# 2.net
KiCad netlist of a schematic drawn in Altium Designer
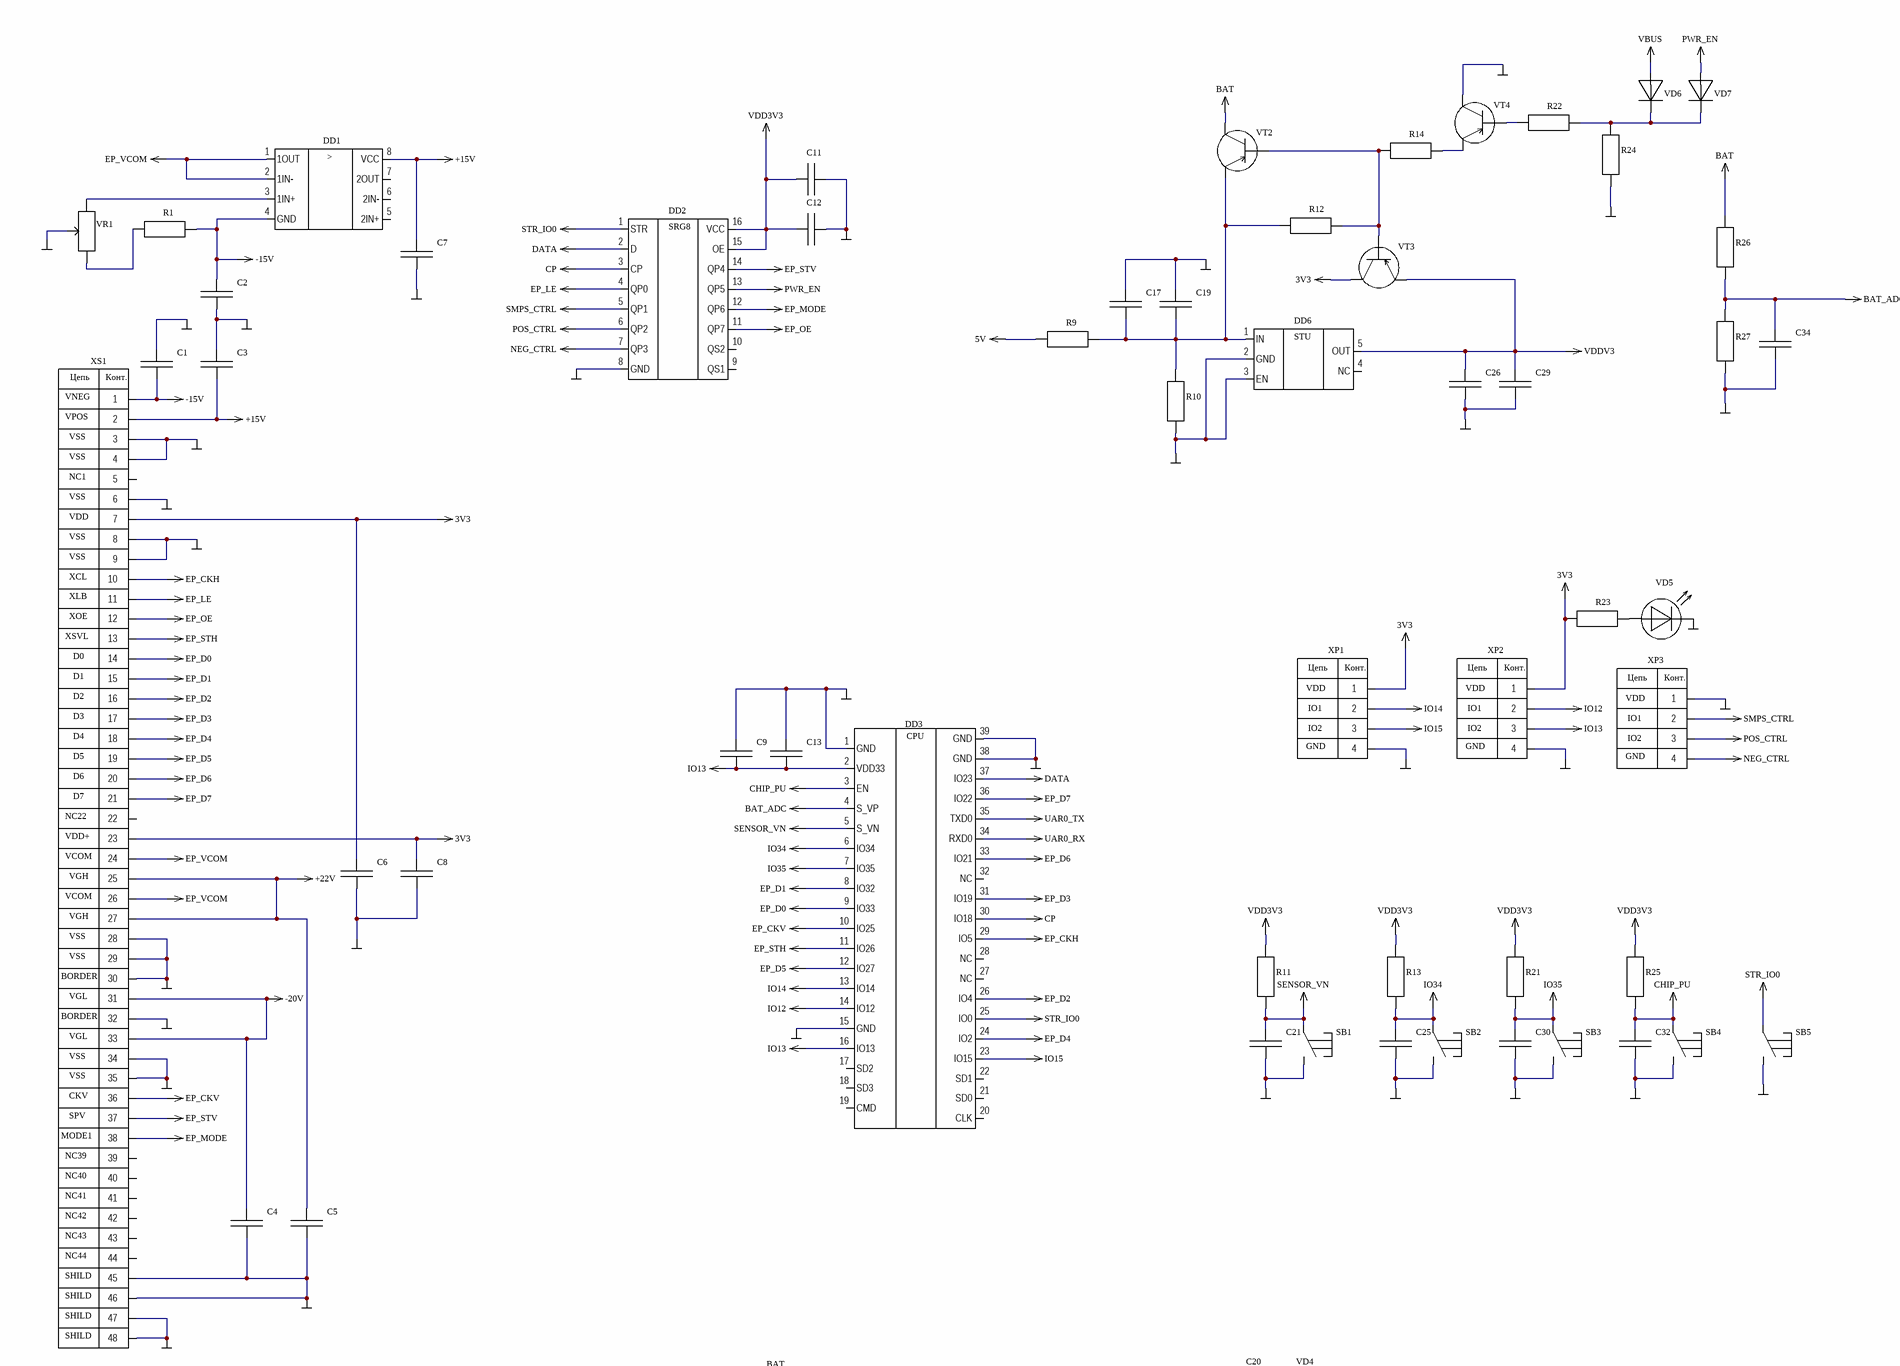
[diagram p0: принципиальная2.schdoc, top left]
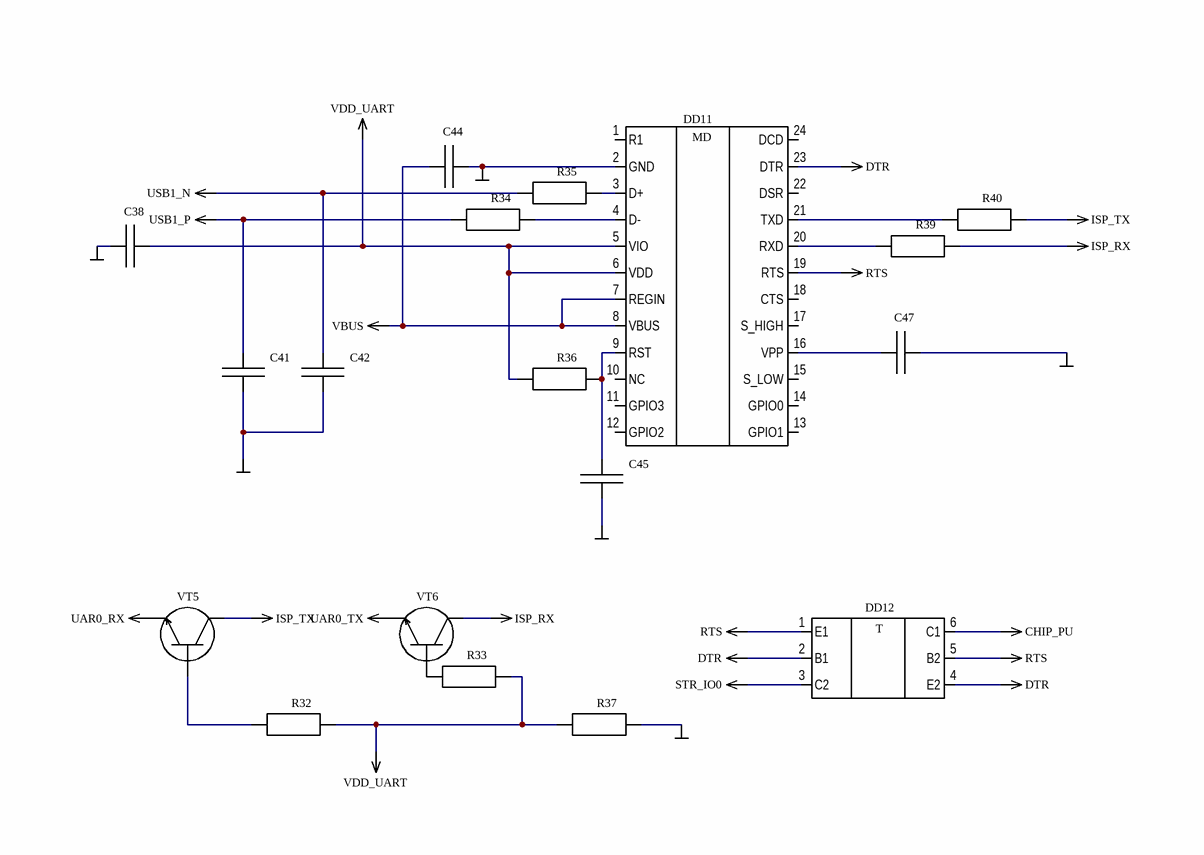
[diagram p1: принципиальная2.schdoc, top right]
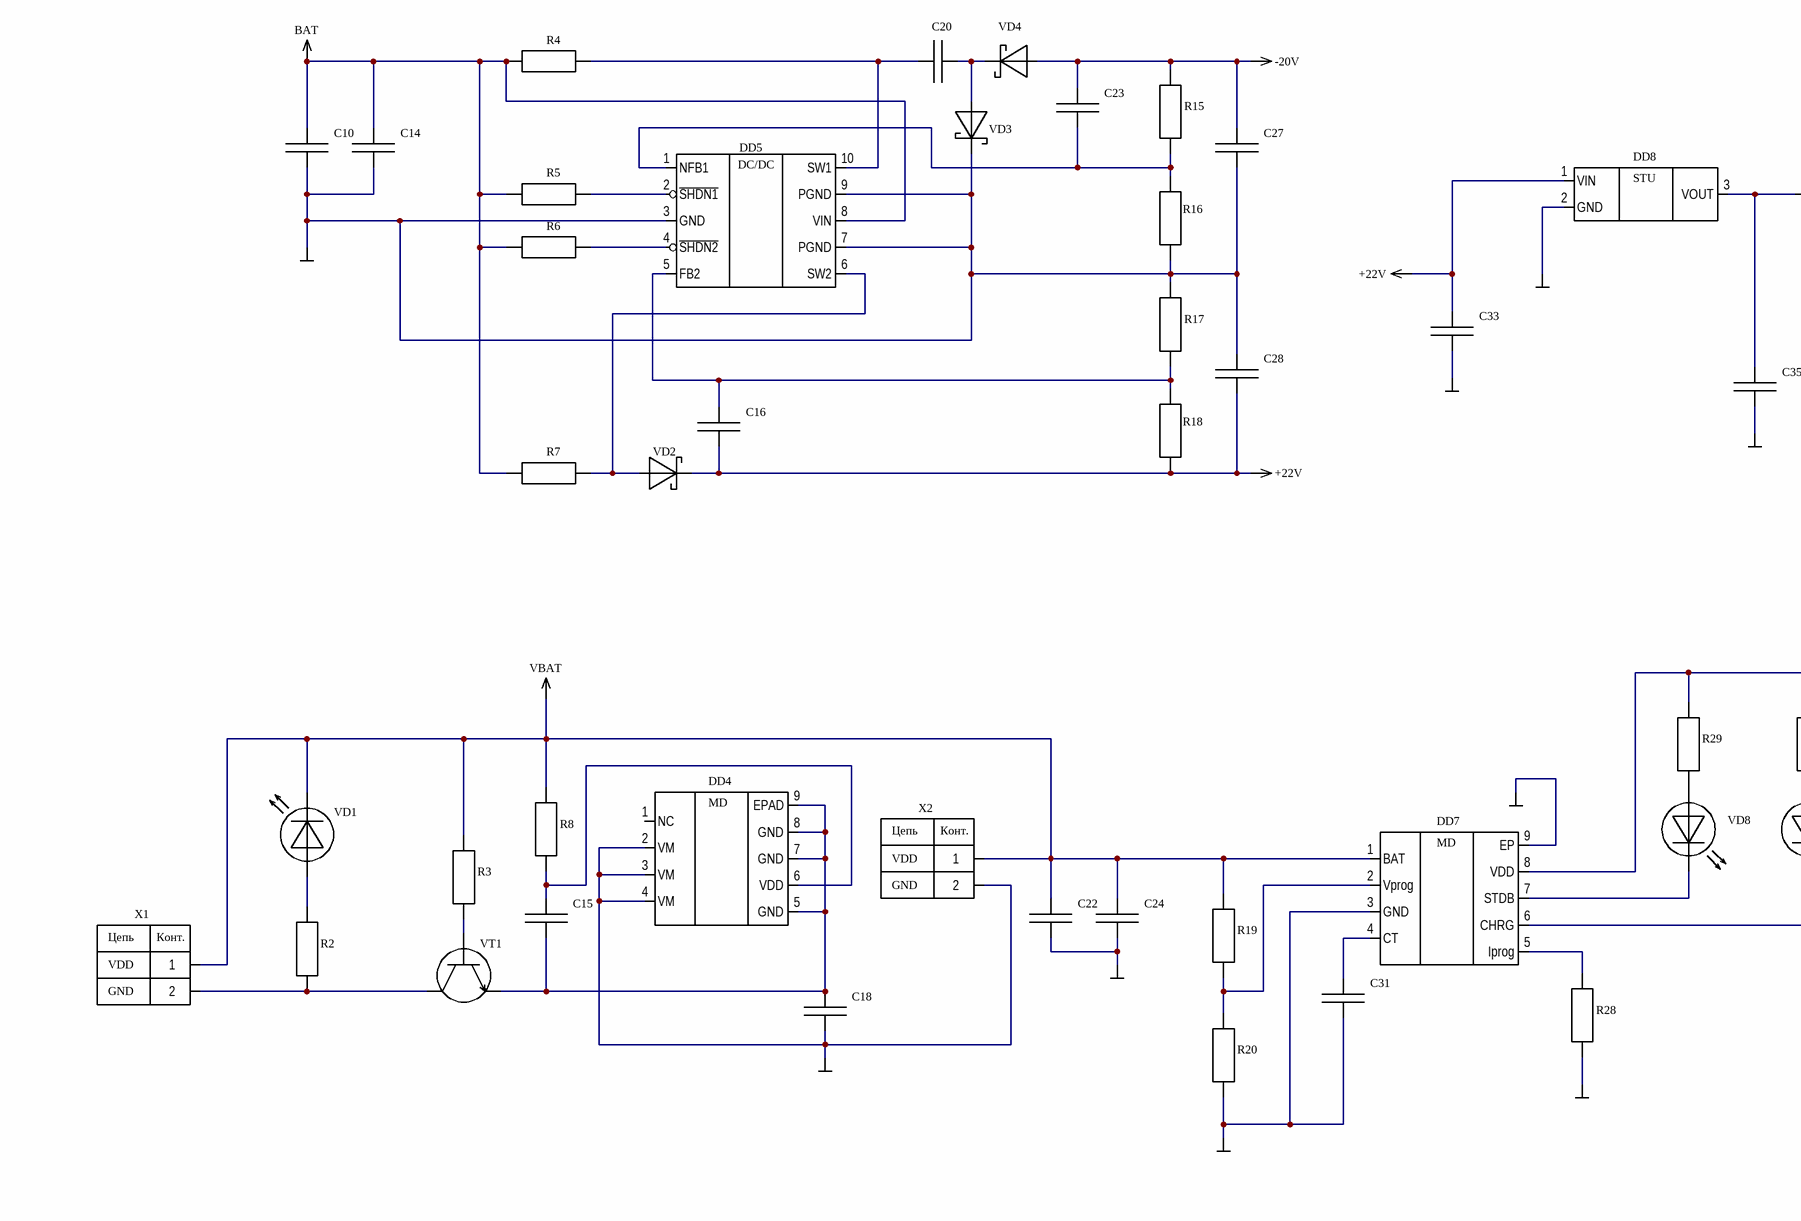
[diagram p2: принципиальная2.schdoc, bottom left]
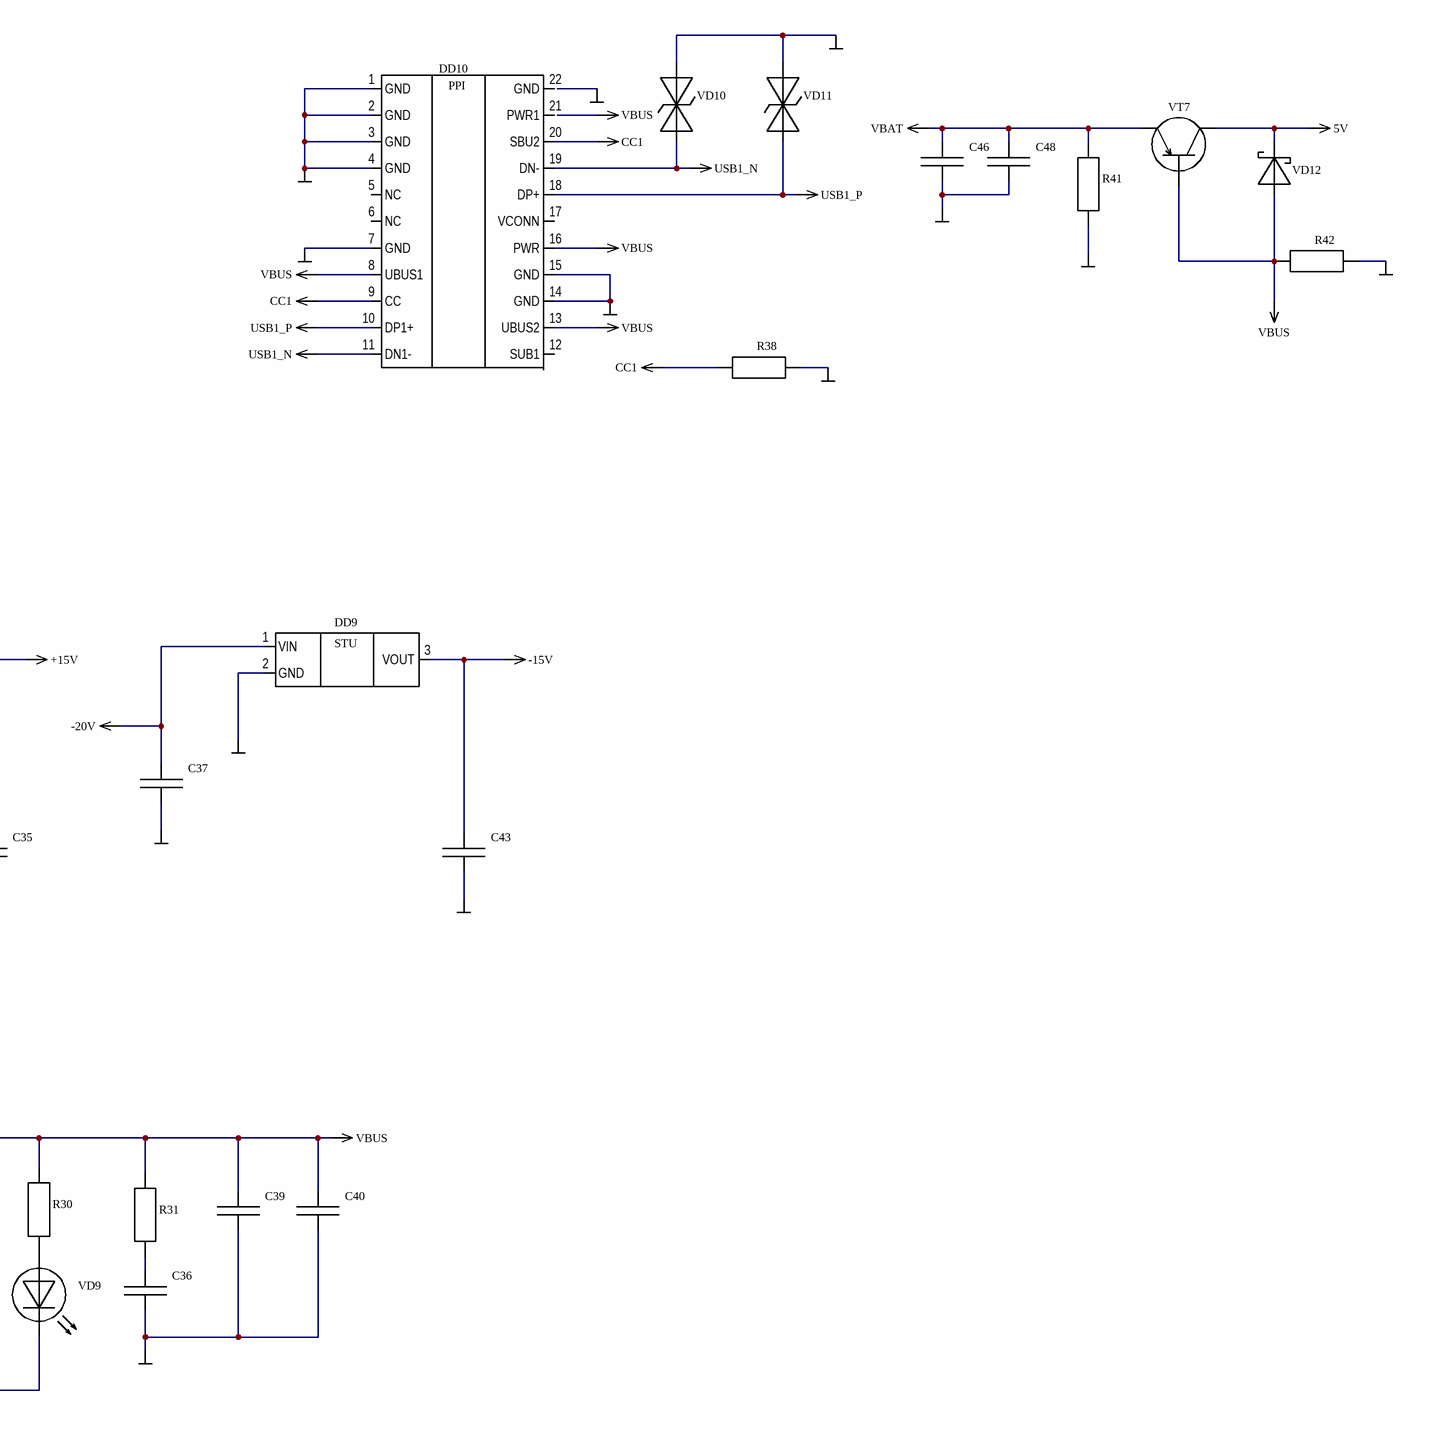
[diagram p3: принципиальная2.schdoc, bottom right]

(export (version "E")
  (design (tool "Eeschema 10.0.6"))
  (components
    (comp (ref "C1")
      (value "Capacitor")
      (footprint "condensator CAP3216X125N:CAP3216X125N")
      (libsource (lib "Library_ugo") (part "Capacitor"))
    )
    (comp (ref "C2")
      (value "Capacitor")
      (footprint "condensator CAP3216X125N:CAP3216X125N")
      (libsource (lib "Library_ugo") (part "Capacitor"))
    )
    (comp (ref "C3")
      (value "Capacitor")
      (footprint "condensator CAP3216X125N:CAP3216X125N")
      (libsource (lib "Library_ugo") (part "Capacitor"))
    )
    (comp (ref "C4")
      (value "Capacitor")
      (footprint "condensator CAP3216X125N:CAP3216X125N")
      (libsource (lib "Library_ugo") (part "Capacitor"))
    )
    (comp (ref "C5")
      (value "Capacitor")
      (footprint "condensator CAP3216X125N:CAP3216X125N")
      (libsource (lib "Library_ugo") (part "Capacitor"))
    )
    (comp (ref "C6")
      (value "Capacitor")
      (footprint "condensator CAP3216X125N:CAP3216X125N")
      (libsource (lib "Library_ugo") (part "Capacitor"))
    )
    (comp (ref "C7")
      (value "Capacitor")
      (footprint "condensator CAP3216X125N:CAP3216X125N")
      (libsource (lib "Library_ugo") (part "Capacitor"))
    )
    (comp (ref "C8")
      (value "Capacitor")
      (footprint "condensator CAP3216X125N:CAP3216X125N")
      (libsource (lib "Library_ugo") (part "Capacitor"))
    )
    (comp (ref "C9")
      (value "Capacitor")
      (footprint "condensator CAP3216X125N:CAP3216X125N")
      (libsource (lib "Library_ugo") (part "Capacitor"))
    )
    (comp (ref "C10")
      (value "Capacitor")
      (footprint "condensator CAP3216X125N:CAP3216X125N")
      (libsource (lib "Library_ugo") (part "Capacitor"))
    )
    (comp (ref "C11")
      (value "Capacitor")
      (footprint "condensator CAP3216X125N:CAP3216X125N")
      (libsource (lib "Library_ugo") (part "Capacitor"))
    )
    (comp (ref "C12")
      (value "Capacitor")
      (footprint "condensator CAP3216X125N:CAP3216X125N")
      (libsource (lib "Library_ugo") (part "Capacitor"))
    )
    (comp (ref "C13")
      (value "Capacitor")
      (footprint "condensator CAP3216X125N:CAP3216X125N")
      (libsource (lib "Library_ugo") (part "Capacitor"))
    )
    (comp (ref "C14")
      (value "Capacitor")
      (footprint "condensator CAP3216X125N:CAP3216X125N")
      (libsource (lib "Library_ugo") (part "Capacitor"))
    )
    (comp (ref "C15")
      (value "Capacitor")
      (footprint "condensator CAP3216X125N:CAP3216X125N")
      (libsource (lib "Library_ugo") (part "Capacitor"))
    )
    (comp (ref "C16")
      (value "Capacitor")
      (footprint "condensator CAP3216X125N:CAP3216X125N")
      (libsource (lib "Library_ugo") (part "Capacitor"))
    )
    (comp (ref "C17")
      (value "Capacitor")
      (footprint "condensator CAP3216X125N:CAP3216X125N")
      (libsource (lib "Library_ugo") (part "Capacitor"))
    )
    (comp (ref "C18")
      (value "Capacitor")
      (footprint "condensator CAP3216X125N:CAP3216X125N")
      (libsource (lib "Library_ugo") (part "Capacitor"))
    )
    (comp (ref "C19")
      (value "Capacitor")
      (footprint "condensator CAP3216X125N:CAP3216X125N")
      (libsource (lib "Library_ugo") (part "Capacitor"))
    )
    (comp (ref "C20")
      (value "Capacitor")
      (footprint "condensator CAP3216X125N:CAP3216X125N")
      (libsource (lib "Library_ugo") (part "Capacitor"))
    )
    (comp (ref "C21")
      (value "Capacitor")
      (footprint "condensator CAP3216X125N:CAP3216X125N")
      (libsource (lib "Library_ugo") (part "Capacitor"))
    )
    (comp (ref "C22")
      (value "Capacitor")
      (footprint "condensator CAP3216X125N:CAP3216X125N")
      (libsource (lib "Library_ugo") (part "Capacitor"))
    )
    (comp (ref "C23")
      (value "Capacitor")
      (footprint "condensator CAP3216X125N:CAP3216X125N")
      (libsource (lib "Library_ugo") (part "Capacitor"))
    )
    (comp (ref "C24")
      (value "Capacitor")
      (footprint "condensator CAP3216X125N:CAP3216X125N")
      (libsource (lib "Library_ugo") (part "Capacitor"))
    )
    (comp (ref "C25")
      (value "Capacitor")
      (footprint "condensator CAP3216X125N:CAP3216X125N")
      (libsource (lib "Library_ugo") (part "Capacitor"))
    )
    (comp (ref "C26")
      (value "Capacitor")
      (footprint "condensator CAP3216X125N:CAP3216X125N")
      (libsource (lib "Library_ugo") (part "Capacitor"))
    )
    (comp (ref "C27")
      (value "Capacitor")
      (footprint "condensator CAP3216X125N:CAP3216X125N")
      (libsource (lib "Library_ugo") (part "Capacitor"))
    )
    (comp (ref "C28")
      (value "Capacitor")
      (footprint "condensator CAP3216X125N:CAP3216X125N")
      (libsource (lib "Library_ugo") (part "Capacitor"))
    )
    (comp (ref "C29")
      (value "Capacitor")
      (footprint "condensator CAP3216X125N:CAP3216X125N")
      (libsource (lib "Library_ugo") (part "Capacitor"))
    )
    (comp (ref "C30")
      (value "Capacitor")
      (footprint "condensator CAP3216X125N:CAP3216X125N")
      (libsource (lib "Library_ugo") (part "Capacitor"))
    )
    (comp (ref "C31")
      (value "Capacitor")
      (footprint "condensator CAP3216X125N:CAP3216X125N")
      (libsource (lib "Library_ugo") (part "Capacitor"))
    )
    (comp (ref "C32")
      (value "Capacitor")
      (footprint "condensator CAP3216X125N:CAP3216X125N")
      (libsource (lib "Library_ugo") (part "Capacitor"))
    )
    (comp (ref "C33")
      (value "Capacitor")
      (footprint "condensator CAP3216X125N:CAP3216X125N")
      (libsource (lib "Library_ugo") (part "Capacitor"))
    )
    (comp (ref "C34")
      (value "Capacitor")
      (footprint "condensator CAP3216X125N:CAP3216X125N")
      (libsource (lib "Library_ugo") (part "Capacitor"))
    )
    (comp (ref "C35")
      (value "Capacitor")
      (footprint "condensator CAP3216X125N:CAP3216X125N")
      (libsource (lib "Library_ugo") (part "Capacitor"))
    )
    (comp (ref "C36")
      (value "Capacitor")
      (footprint "condensator CAP3216X125N:CAP3216X125N")
      (libsource (lib "Library_ugo") (part "Capacitor"))
    )
    (comp (ref "C37")
      (value "Capacitor")
      (footprint "condensator CAP3216X125N:CAP3216X125N")
      (libsource (lib "Library_ugo") (part "Capacitor"))
    )
    (comp (ref "C38")
      (value "Capacitor")
      (footprint "condensator CAP3216X125N:CAP3216X125N")
      (libsource (lib "Library_ugo") (part "Capacitor"))
    )
    (comp (ref "C39")
      (value "Capacitor")
      (footprint "condensator CAP3216X125N:CAP3216X125N")
      (libsource (lib "Library_ugo") (part "Capacitor"))
    )
    (comp (ref "C40")
      (value "Capacitor")
      (footprint "condensator CAP3216X125N:CAP3216X125N")
      (libsource (lib "Library_ugo") (part "Capacitor"))
    )
    (comp (ref "C41")
      (value "Capacitor")
      (footprint "condensator CAP3216X125N:CAP3216X125N")
      (libsource (lib "Library_ugo") (part "Capacitor"))
    )
    (comp (ref "C42")
      (value "Capacitor")
      (footprint "condensator CAP3216X125N:CAP3216X125N")
      (libsource (lib "Library_ugo") (part "Capacitor"))
    )
    (comp (ref "C43")
      (value "Capacitor")
      (footprint "condensator CAP3216X125N:CAP3216X125N")
      (libsource (lib "Library_ugo") (part "Capacitor"))
    )
    (comp (ref "C44")
      (value "Capacitor")
      (footprint "condensator CAP3216X125N:CAP3216X125N")
      (libsource (lib "Library_ugo") (part "Capacitor"))
    )
    (comp (ref "C45")
      (value "Capacitor")
      (footprint "condensator CAP3216X125N:CAP3216X125N")
      (libsource (lib "Library_ugo") (part "Capacitor"))
    )
    (comp (ref "C46")
      (value "Capacitor")
      (footprint "condensator CAP3216X125N:CAP3216X125N")
      (libsource (lib "Library_ugo") (part "Capacitor"))
    )
    (comp (ref "C47")
      (value "Capacitor")
      (footprint "condensator CAP3216X125N:CAP3216X125N")
      (libsource (lib "Library_ugo") (part "Capacitor"))
    )
    (comp (ref "C48")
      (value "Capacitor")
      (footprint "condensator CAP3216X125N:CAP3216X125N")
      (libsource (lib "Library_ugo") (part "Capacitor"))
    )
    (comp (ref "DD1")
      (value "LM358DR2G")
      (footprint "SOIC127P599X175-8N:SOIC127P599X175-8N")
      (libsource (lib "Library_ugo") (part "LM358DR2G"))
    )
    (comp (ref "DD2")
      (value "74HCT4094D")
      (footprint "SOIC127P1030X265-16N:SOIC127P1030X265-16N")
      (libsource (lib "Library_ugo") (part "74HCT4094D"))
    )
    (comp (ref "DD3")
      (value "ESP32-WROVER-E")
      (footprint "SnapEDApcb:XCVR_ESP32-WROVER")
      (libsource (lib "Library_ugo") (part "ESP32-WROVER-E"))
    )
    (comp (ref "DD4")
      (value "IP3005A")
      (footprint "SI2301:ESOP-8_L4.9-W3.9-P1.27-LS6.0-BL-EP")
      (libsource (lib "Library_ugo") (part "IP3005A"))
    )
    (comp (ref "DD5")
      (value "LT1945")
      (footprint "MSOP-10_MS:MSOP-10_MS")
      (libsource (lib "Library_ugo") (part "LT1945"))
    )
    (comp (ref "DD6")
      (value "AP2112K")
      (footprint "SnapEDApcb:SOT95P280X145-5N")
      (libsource (lib "Library_ugo") (part "AP2112K"))
    )
    (comp (ref "DD7")
      (value "HX6610S")
      (footprint "SI2301:ESOP-8_L4.9-W3.9-P1.27-LS6.0-BL-EP")
      (libsource (lib "Library_ugo") (part "HX6610S"))
    )
    (comp (ref "DD8")
      (value "CJ78L15")
      (footprint "SnapEDApcb:REG_MCP1702T-3302E/MB")
      (libsource (lib "Library_ugo") (part "CJ78L15"))
    )
    (comp (ref "DD9")
      (value "CJ78L15")
      (footprint "SnapEDApcb:REG_MCP1702T-3302E/MB")
      (libsource (lib "Library_ugo") (part "CJ78L15"))
    )
    (comp (ref "DD10")
      (value "TYPE C")
      (footprint "SnapEDApcb:QFN50P400X400X80-25N")
      (libsource (lib "Library_ugo") (part "TYPE C"))
    )
    (comp (ref "DD11")
      (value "CP2014")
      (footprint "SnapEDApcb:QFN50P400X400X80-25N")
      (libsource (lib "Library_ugo") (part "CP2014"))
    )
    (comp (ref "DD12")
      (value "UMH3N")
      (footprint "SnapEDApcb:SOP65P210X100-6N")
      (libsource (lib "Library_ugo") (part "UMH3N"))
    )
    (comp (ref "R1")
      (value "Resistor")
      (footprint "Library_footprint:res0603")
      (libsource (lib "Library_ugo") (part "Resistor"))
    )
    (comp (ref "R2")
      (value "Resistor")
      (footprint "Library_footprint:res0603")
      (libsource (lib "Library_ugo") (part "Resistor"))
    )
    (comp (ref "R3")
      (value "Resistor")
      (footprint "Library_footprint:res0603")
      (libsource (lib "Library_ugo") (part "Resistor"))
    )
    (comp (ref "R4")
      (value "Resistor")
      (footprint "Library_footprint:res0603")
      (libsource (lib "Library_ugo") (part "Resistor"))
    )
    (comp (ref "R5")
      (value "Resistor")
      (footprint "Library_footprint:res0603")
      (libsource (lib "Library_ugo") (part "Resistor"))
    )
    (comp (ref "R6")
      (value "Resistor")
      (footprint "Library_footprint:res0603")
      (libsource (lib "Library_ugo") (part "Resistor"))
    )
    (comp (ref "R7")
      (value "Resistor")
      (footprint "Library_footprint:res0603")
      (libsource (lib "Library_ugo") (part "Resistor"))
    )
    (comp (ref "R8")
      (value "Resistor")
      (footprint "Library_footprint:res0603")
      (libsource (lib "Library_ugo") (part "Resistor"))
    )
    (comp (ref "R9")
      (value "Resistor")
      (footprint "Library_footprint:res0603")
      (libsource (lib "Library_ugo") (part "Resistor"))
    )
    (comp (ref "R10")
      (value "Resistor")
      (footprint "Library_footprint:res0603")
      (libsource (lib "Library_ugo") (part "Resistor"))
    )
    (comp (ref "R11")
      (value "Resistor")
      (footprint "Library_footprint:res0603")
      (libsource (lib "Library_ugo") (part "Resistor"))
    )
    (comp (ref "R12")
      (value "Resistor")
      (footprint "Library_footprint:res0603")
      (libsource (lib "Library_ugo") (part "Resistor"))
    )
    (comp (ref "R13")
      (value "Resistor")
      (footprint "Library_footprint:res0603")
      (libsource (lib "Library_ugo") (part "Resistor"))
    )
    (comp (ref "R14")
      (value "Resistor")
      (footprint "Library_footprint:res0603")
      (libsource (lib "Library_ugo") (part "Resistor"))
    )
    (comp (ref "R15")
      (value "Resistor")
      (footprint "Library_footprint:res0603")
      (libsource (lib "Library_ugo") (part "Resistor"))
    )
    (comp (ref "R16")
      (value "Resistor")
      (footprint "Library_footprint:res0603")
      (libsource (lib "Library_ugo") (part "Resistor"))
    )
    (comp (ref "R17")
      (value "Resistor")
      (footprint "Library_footprint:res0603")
      (libsource (lib "Library_ugo") (part "Resistor"))
    )
    (comp (ref "R18")
      (value "Resistor")
      (footprint "Library_footprint:res0603")
      (libsource (lib "Library_ugo") (part "Resistor"))
    )
    (comp (ref "R19")
      (value "Resistor")
      (footprint "Library_footprint:res0603")
      (libsource (lib "Library_ugo") (part "Resistor"))
    )
    (comp (ref "R20")
      (value "Resistor")
      (footprint "Library_footprint:res0603")
      (libsource (lib "Library_ugo") (part "Resistor"))
    )
    (comp (ref "R21")
      (value "Resistor")
      (footprint "Library_footprint:res0603")
      (libsource (lib "Library_ugo") (part "Resistor"))
    )
    (comp (ref "R22")
      (value "Resistor")
      (footprint "Library_footprint:res0603")
      (libsource (lib "Library_ugo") (part "Resistor"))
    )
    (comp (ref "R23")
      (value "Resistor")
      (footprint "Library_footprint:res0603")
      (libsource (lib "Library_ugo") (part "Resistor"))
    )
    (comp (ref "R24")
      (value "Resistor")
      (footprint "Library_footprint:res0603")
      (libsource (lib "Library_ugo") (part "Resistor"))
    )
    (comp (ref "R25")
      (value "Resistor")
      (footprint "Library_footprint:res0603")
      (libsource (lib "Library_ugo") (part "Resistor"))
    )
    (comp (ref "R26")
      (value "Resistor")
      (footprint "Library_footprint:res0603")
      (libsource (lib "Library_ugo") (part "Resistor"))
    )
    (comp (ref "R27")
      (value "Resistor")
      (footprint "Library_footprint:res0603")
      (libsource (lib "Library_ugo") (part "Resistor"))
    )
    (comp (ref "R28")
      (value "Resistor")
      (footprint "Library_footprint:res0603")
      (libsource (lib "Library_ugo") (part "Resistor"))
    )
    (comp (ref "R29")
      (value "Resistor")
      (footprint "Library_footprint:res0603")
      (libsource (lib "Library_ugo") (part "Resistor"))
    )
    (comp (ref "R30")
      (value "Resistor")
      (footprint "Library_footprint:res0603")
      (libsource (lib "Library_ugo") (part "Resistor"))
    )
    (comp (ref "R31")
      (value "Resistor")
      (footprint "Library_footprint:res0603")
      (libsource (lib "Library_ugo") (part "Resistor"))
    )
    (comp (ref "R32")
      (value "Resistor")
      (footprint "Library_footprint:res0603")
      (libsource (lib "Library_ugo") (part "Resistor"))
    )
    (comp (ref "R33")
      (value "Resistor")
      (footprint "Library_footprint:res0603")
      (libsource (lib "Library_ugo") (part "Resistor"))
    )
    (comp (ref "R34")
      (value "Resistor")
      (footprint "Library_footprint:res0603")
      (libsource (lib "Library_ugo") (part "Resistor"))
    )
    (comp (ref "R35")
      (value "Resistor")
      (footprint "Library_footprint:res0603")
      (libsource (lib "Library_ugo") (part "Resistor"))
    )
    (comp (ref "R36")
      (value "Resistor")
      (footprint "Library_footprint:res0603")
      (libsource (lib "Library_ugo") (part "Resistor"))
    )
    (comp (ref "R37")
      (value "Resistor")
      (footprint "Library_footprint:res0603")
      (libsource (lib "Library_ugo") (part "Resistor"))
    )
    (comp (ref "R38")
      (value "Resistor")
      (footprint "Library_footprint:res0603")
      (libsource (lib "Library_ugo") (part "Resistor"))
    )
    (comp (ref "R39")
      (value "Resistor")
      (footprint "Library_footprint:res0603")
      (libsource (lib "Library_ugo") (part "Resistor"))
    )
    (comp (ref "R40")
      (value "Resistor")
      (footprint "Library_footprint:res0603")
      (libsource (lib "Library_ugo") (part "Resistor"))
    )
    (comp (ref "R41")
      (value "Resistor")
      (footprint "Library_footprint:res0603")
      (libsource (lib "Library_ugo") (part "Resistor"))
    )
    (comp (ref "R42")
      (value "Resistor")
      (footprint "Library_footprint:res0603")
      (libsource (lib "Library_ugo") (part "Resistor"))
    )
    (comp (ref "SB1")
      (value "button")
      (footprint "SnapEDApcb:SW_147873-1")
      (libsource (lib "Library_ugo") (part "button"))
    )
    (comp (ref "SB2")
      (value "button")
      (footprint "SnapEDApcb:SW_147873-1")
      (libsource (lib "Library_ugo") (part "button"))
    )
    (comp (ref "SB3")
      (value "button")
      (footprint "SnapEDApcb:SW_147873-1")
      (libsource (lib "Library_ugo") (part "button"))
    )
    (comp (ref "SB4")
      (value "button")
      (footprint "SnapEDApcb:SW_147873-1")
      (libsource (lib "Library_ugo") (part "button"))
    )
    (comp (ref "SB5")
      (value "button")
      (footprint "SnapEDApcb:SW_147873-1")
      (libsource (lib "Library_ugo") (part "button"))
    )
    (comp (ref "VD1")
      (value "LED diode")
      (footprint "led diode:BEADC0603X33N")
      (libsource (lib "Library_ugo") (part "LED diode"))
    )
    (comp (ref "VD2")
      (value "1N5819")
      (footprint "SOD3715X145N:SOD3715X145N")
      (libsource (lib "Library_ugo") (part "1N5819"))
    )
    (comp (ref "VD3")
      (value "1N5819")
      (footprint "SOD3715X145N:SOD3715X145N")
      (libsource (lib "Library_ugo") (part "1N5819"))
    )
    (comp (ref "VD4")
      (value "1N5819")
      (footprint "SOD3715X145N:SOD3715X145N")
      (libsource (lib "Library_ugo") (part "1N5819"))
    )
    (comp (ref "VD5")
      (value "LED diode")
      (footprint "led diode:BEADC0603X33N")
      (libsource (lib "Library_ugo") (part "LED diode"))
    )
    (comp (ref "VD6")
      (value "Diod")
      (footprint "SnapEDApcb:SODFL1608X70N")
      (libsource (lib "Library_ugo") (part "Diod"))
    )
    (comp (ref "VD7")
      (value "Diod")
      (footprint "SnapEDApcb:SODFL1608X70N")
      (libsource (lib "Library_ugo") (part "Diod"))
    )
    (comp (ref "VD8")
      (value "LED diode")
      (footprint "led diode:BEADC0603X33N")
      (libsource (lib "Library_ugo") (part "LED diode"))
    )
    (comp (ref "VD9")
      (value "LED diode")
      (footprint "led diode:BEADC0603X33N")
      (libsource (lib "Library_ugo") (part "LED diode"))
    )
    (comp (ref "VD10")
      (value "ESD diode")
      (footprint "SnapEDApcb:SOD523")
      (libsource (lib "Library_ugo") (part "ESD diode"))
    )
    (comp (ref "VD11")
      (value "ESD diode")
      (footprint "SnapEDApcb:SOD523")
      (libsource (lib "Library_ugo") (part "ESD diode"))
    )
    (comp (ref "VD12")
      (value "1N5819")
      (footprint "SOD3715X145N:SOD3715X145N")
      (libsource (lib "Library_ugo") (part "1N5819"))
    )
    (comp (ref "VR1")
      (value "TRIMPOT-SMD-3MM")
      (footprint "SOIC127P599X175-8N:TRIMPOT-SMD-TC33X")
      (libsource (lib "Library_ugo") (part "TRIMPOT-SMD-3MM"))
    )
    (comp (ref "VT1")
      (value "Transistor(npn)")
      (footprint "SI2301:SOT23-3P96_237X112L42X44")
      (libsource (lib "Library_ugo") (part "Transistor(npn)"))
    )
    (comp (ref "VT2")
      (value "Transistor(pnp)")
      (footprint "SI2301:SOT23-3P96_237X112L42X44")
      (libsource (lib "Library_ugo") (part "Transistor(pnp)"))
    )
    (comp (ref "VT3")
      (value "Transistor(pnp)")
      (footprint "SI2301:SOT23-3P96_237X112L42X44")
      (libsource (lib "Library_ugo") (part "Transistor(pnp)"))
    )
    (comp (ref "VT4")
      (value "Transistor(pnp)")
      (footprint "SI2301:SOT23-3P96_237X112L42X44")
      (libsource (lib "Library_ugo") (part "Transistor(pnp)"))
    )
    (comp (ref "VT5")
      (value "Transistor(npn)")
      (footprint "SI2301:SOT23-3P96_237X112L42X44")
      (libsource (lib "Library_ugo") (part "Transistor(npn)"))
    )
    (comp (ref "VT6")
      (value "Transistor(npn)")
      (footprint "SI2301:SOT23-3P96_237X112L42X44")
      (libsource (lib "Library_ugo") (part "Transistor(npn)"))
    )
    (comp (ref "VT7")
      (value "Transistor(pnp)")
      (footprint "SI2301:SOT23-3P96_237X112L42X44")
      (libsource (lib "Library_ugo") (part "Transistor(pnp)"))
    )
    (comp (ref "X1") (value "2P") (footprint "SI2301:2P") (libsource (lib "Library_ugo") (part "2P")))
    (comp (ref "X2") (value "2P") (footprint "SI2301:2P") (libsource (lib "Library_ugo") (part "2P")))
    (comp (ref "XP1")
      (value "MOLEX P4")
      (footprint "SnapEDApcb:MOLEX_15244441")
      (libsource (lib "Library_ugo") (part "MOLEX P4"))
    )
    (comp (ref "XP2")
      (value "MOLEX P4")
      (footprint "SnapEDApcb:MOLEX_15244441")
      (libsource (lib "Library_ugo") (part "MOLEX P4"))
    )
    (comp (ref "XP3")
      (value "MOLEX P4")
      (footprint "SnapEDApcb:MOLEX_15244441")
      (libsource (lib "Library_ugo") (part "MOLEX P4"))
    )
    (comp (ref "XS1")
      (value "DVI")
      (footprint "GCT_FFC2B28-22-G_REVA:GCT_FFC2B28-22-G_REVA")
      (libsource (lib "Library_ugo") (part "DVI"))
    )
  )
  (nets
    (net (code "1") (name "+15V") (class "Default")
      (node (ref "C3") (pin "2") (pinfunction "A_2") (pintype "passive"))
      (node (ref "C35") (pin "1") (pinfunction "A_1") (pintype "passive"))
      (node (ref "C7") (pin "1") (pinfunction "A_1") (pintype "passive"))
      (node (ref "DD1") (pin "8") (pinfunction "VCC_8") (pintype "passive"))
      (node (ref "DD8") (pin "3") (pinfunction "VOUT_3") (pintype "passive"))
      (node (ref "XS1") (pin "2") (pinfunction "2_2") (pintype "passive"))
    )
    (net (code "2") (name "+22V") (class "Default")
      (node (ref "C16") (pin "2") (pinfunction "A_2") (pintype "passive"))
      (node (ref "C28") (pin "2") (pinfunction "A_2") (pintype "passive"))
      (node (ref "C33") (pin "1") (pinfunction "A_1") (pintype "passive"))
      (node (ref "C5") (pin "1") (pinfunction "A_1") (pintype "passive"))
      (node (ref "DD8") (pin "1") (pinfunction "VIN_1") (pintype "passive"))
      (node (ref "R18") (pin "1") (pinfunction "A_1") (pintype "passive"))
      (node (ref "VD2") (pin "2") (pinfunction "B_2") (pintype "passive"))
      (node (ref "XS1") (pin "25") (pinfunction "25_25") (pintype "passive"))
      (node (ref "XS1") (pin "27") (pinfunction "27_27") (pintype "passive"))
    )
    (net (code "3") (name "-15V") (class "Default")
      (node (ref "C1") (pin "2") (pinfunction "A_2") (pintype "passive"))
      (node (ref "C2") (pin "1") (pinfunction "A_1") (pintype "passive"))
      (node (ref "C43") (pin "1") (pinfunction "A_1") (pintype "passive"))
      (node (ref "DD1") (pin "4") (pinfunction "GND_4") (pintype "passive"))
      (node (ref "DD9") (pin "3") (pinfunction "VOUT_3") (pintype "passive"))
      (node (ref "R1") (pin "2") (pinfunction "B_2") (pintype "passive"))
      (node (ref "XS1") (pin "1") (pinfunction "1_1") (pintype "passive"))
    )
    (net (code "4") (name "-20V") (class "Default")
      (node (ref "C23") (pin "1") (pinfunction "A_1") (pintype "passive"))
      (node (ref "C27") (pin "1") (pinfunction "A_1") (pintype "passive"))
      (node (ref "C37") (pin "1") (pinfunction "A_1") (pintype "passive"))
      (node (ref "C4") (pin "1") (pinfunction "A_1") (pintype "passive"))
      (node (ref "DD9") (pin "1") (pinfunction "VIN_1") (pintype "passive"))
      (node (ref "R15") (pin "2") (pinfunction "B_2") (pintype "passive"))
      (node (ref "VD4") (pin "1") (pinfunction "A_1") (pintype "passive"))
      (node (ref "XS1") (pin "31") (pinfunction "31_31") (pintype "passive"))
      (node (ref "XS1") (pin "33") (pinfunction "33_33") (pintype "passive"))
    )
    (net (code "5") (name "3V3") (class "Default")
      (node (ref "C6") (pin "1") (pinfunction "A_1") (pintype "passive"))
      (node (ref "C8") (pin "1") (pinfunction "A_1") (pintype "passive"))
      (node (ref "R23") (pin "1") (pinfunction "A_1") (pintype "passive"))
      (node (ref "VT3") (pin "2") (pinfunction "B_2") (pintype "passive"))
      (node (ref "XP1") (pin "1") (pinfunction "1_1") (pintype "passive"))
      (node (ref "XP2") (pin "1") (pinfunction "1_1") (pintype "passive"))
      (node (ref "XS1") (pin "23") (pinfunction "23_23") (pintype "passive"))
      (node (ref "XS1") (pin "7") (pinfunction "7_7") (pintype "passive"))
    )
    (net (code "6") (name "5V") (class "Default")
      (node (ref "R9") (pin "1") (pinfunction "A_1") (pintype "passive"))
      (node (ref "VD12") (pin "2") (pinfunction "B_2") (pintype "passive"))
      (node (ref "VT7") (pin "2") (pinfunction "B_2") (pintype "passive"))
    )
    (net (code "7") (name "BAT") (class "Default")
      (node (ref "C10") (pin "1") (pinfunction "A_1") (pintype "passive"))
      (node (ref "C14") (pin "1") (pinfunction "A_1") (pintype "passive"))
      (node (ref "DD5") (pin "8") (pinfunction "VIN_8") (pintype "passive"))
      (node (ref "R26") (pin "2") (pinfunction "B_2") (pintype "passive"))
      (node (ref "R4") (pin "1") (pinfunction "A_1") (pintype "passive"))
      (node (ref "R5") (pin "1") (pinfunction "A_1") (pintype "passive"))
      (node (ref "R6") (pin "1") (pinfunction "A_1") (pintype "passive"))
      (node (ref "R7") (pin "1") (pinfunction "A_1") (pintype "passive"))
      (node (ref "VT2") (pin "2") (pinfunction "B_2") (pintype "passive"))
    )
    (net (code "8") (name "BAT_ADC") (class "Default")
      (node (ref "C34") (pin "1") (pinfunction "A_1") (pintype "passive"))
      (node (ref "DD3") (pin "4") (pinfunction "S_VP_4") (pintype "passive"))
      (node (ref "R26") (pin "1") (pinfunction "A_1") (pintype "passive"))
      (node (ref "R27") (pin "2") (pinfunction "B_2") (pintype "passive"))
    )
    (net (code "9") (name "CC1") (class "Default")
      (node (ref "DD10") (pin "20") (pinfunction "SBU2_20") (pintype "passive"))
      (node (ref "DD10") (pin "9") (pinfunction "CC_9") (pintype "passive"))
      (node (ref "R38") (pin "1") (pinfunction "A_1") (pintype "passive"))
    )
    (net (code "10") (name "CHIP_PU") (class "Default")
      (node (ref "C32") (pin "2") (pinfunction "A_2") (pintype "passive"))
      (node (ref "DD12") (pin "6") (pinfunction "C1_6") (pintype "passive"))
      (node (ref "DD3") (pin "3") (pinfunction "EN_3") (pintype "passive"))
      (node (ref "R25") (pin "1") (pinfunction "A_1") (pintype "passive"))
      (node (ref "SB4") (pin "1") (pinfunction "1_1") (pintype "passive"))
    )
    (net (code "11") (name "CP") (class "Default")
      (node (ref "DD2") (pin "3") (pinfunction "CP_3") (pintype "passive"))
      (node (ref "DD3") (pin "30") (pinfunction "IO18_30") (pintype "passive"))
    )
    (net (code "12") (name "DATA") (class "Default")
      (node (ref "DD2") (pin "2") (pinfunction "D_2") (pintype "passive"))
      (node (ref "DD3") (pin "37") (pinfunction "IO23_37") (pintype "passive"))
    )
    (net (code "13") (name "DTR") (class "Default")
      (node (ref "DD11") (pin "23") (pinfunction "DTR_23") (pintype "passive"))
      (node (ref "DD12") (pin "2") (pinfunction "B1_2") (pintype "passive"))
      (node (ref "DD12") (pin "4") (pinfunction "E2_4") (pintype "passive"))
    )
    (net (code "14") (name "EP_CKH") (class "Default")
      (node (ref "DD3") (pin "29") (pinfunction "IO5_29") (pintype "passive"))
      (node (ref "XS1") (pin "10") (pinfunction "10_10") (pintype "passive"))
    )
    (net (code "15") (name "EP_CKV") (class "Default")
      (node (ref "DD3") (pin "10") (pinfunction "IO25_10") (pintype "passive"))
      (node (ref "XS1") (pin "36") (pinfunction "36_36") (pintype "passive"))
    )
    (net (code "16") (name "EP_D0") (class "Default")
      (node (ref "DD3") (pin "9") (pinfunction "IO33_9") (pintype "passive"))
      (node (ref "XS1") (pin "14") (pinfunction "14_14") (pintype "passive"))
    )
    (net (code "17") (name "EP_D1") (class "Default")
      (node (ref "DD3") (pin "8") (pinfunction "IO32_8") (pintype "passive"))
      (node (ref "XS1") (pin "15") (pinfunction "15_15") (pintype "passive"))
    )
    (net (code "18") (name "EP_D2") (class "Default")
      (node (ref "DD3") (pin "26") (pinfunction "IO4_26") (pintype "passive"))
      (node (ref "XS1") (pin "16") (pinfunction "16_16") (pintype "passive"))
    )
    (net (code "19") (name "EP_D3") (class "Default")
      (node (ref "DD3") (pin "31") (pinfunction "IO19_31") (pintype "passive"))
      (node (ref "XS1") (pin "17") (pinfunction "17_17") (pintype "passive"))
    )
    (net (code "20") (name "EP_D4") (class "Default")
      (node (ref "DD3") (pin "24") (pinfunction "IO2_24") (pintype "passive"))
      (node (ref "XS1") (pin "18") (pinfunction "18_18") (pintype "passive"))
    )
    (net (code "21") (name "EP_D5") (class "Default")
      (node (ref "DD3") (pin "12") (pinfunction "IO27_12") (pintype "passive"))
      (node (ref "XS1") (pin "19") (pinfunction "19_19") (pintype "passive"))
    )
    (net (code "22") (name "EP_D6") (class "Default")
      (node (ref "DD3") (pin "33") (pinfunction "IO21_33") (pintype "passive"))
      (node (ref "XS1") (pin "20") (pinfunction "20_20") (pintype "passive"))
    )
    (net (code "23") (name "EP_D7") (class "Default")
      (node (ref "DD3") (pin "36") (pinfunction "IO22_36") (pintype "passive"))
      (node (ref "XS1") (pin "21") (pinfunction "21_21") (pintype "passive"))
    )
    (net (code "24") (name "EP_LE") (class "Default")
      (node (ref "DD2") (pin "4") (pinfunction "QP0_4") (pintype "passive"))
      (node (ref "XS1") (pin "11") (pinfunction "11_11") (pintype "passive"))
    )
    (net (code "25") (name "EP_MODE") (class "Default")
      (node (ref "DD2") (pin "12") (pinfunction "QP6_12") (pintype "passive"))
      (node (ref "XS1") (pin "38") (pinfunction "38_38") (pintype "passive"))
    )
    (net (code "26") (name "EP_OE") (class "Default")
      (node (ref "DD2") (pin "11") (pinfunction "QP7_11") (pintype "passive"))
      (node (ref "XS1") (pin "12") (pinfunction "12_12") (pintype "passive"))
    )
    (net (code "27") (name "EP_STH") (class "Default")
      (node (ref "DD3") (pin "11") (pinfunction "IO26_11") (pintype "passive"))
      (node (ref "XS1") (pin "13") (pinfunction "13_13") (pintype "passive"))
    )
    (net (code "28") (name "EP_STV") (class "Default")
      (node (ref "DD2") (pin "14") (pinfunction "QP4_14") (pintype "passive"))
      (node (ref "XS1") (pin "37") (pinfunction "37_37") (pintype "passive"))
    )
    (net (code "29") (name "EP_VCOM") (class "Default")
      (node (ref "DD1") (pin "1") (pinfunction "1OUT_1") (pintype "passive"))
      (node (ref "DD1") (pin "2") (pinfunction "1IN-_2") (pintype "passive"))
      (node (ref "XS1") (pin "24") (pinfunction "24_24") (pintype "passive"))
      (node (ref "XS1") (pin "26") (pinfunction "26_26") (pintype "passive"))
    )
    (net (code "30") (name "GND") (class "Default")
      (node (ref "C1") (pin "1") (pinfunction "A_1") (pintype "passive"))
      (node (ref "C10") (pin "2") (pinfunction "A_2") (pintype "passive"))
      (node (ref "C11") (pin "1") (pinfunction "A_1") (pintype "passive"))
      (node (ref "C12") (pin "1") (pinfunction "A_1") (pintype "passive"))
      (node (ref "C13") (pin "1") (pinfunction "A_1") (pintype "passive"))
      (node (ref "C14") (pin "2") (pinfunction "A_2") (pintype "passive"))
      (node (ref "C17") (pin "1") (pinfunction "A_1") (pintype "passive"))
      (node (ref "C18") (pin "2") (pinfunction "A_2") (pintype "passive"))
      (node (ref "C19") (pin "1") (pinfunction "A_1") (pintype "passive"))
      (node (ref "C2") (pin "2") (pinfunction "A_2") (pintype "passive"))
      (node (ref "C21") (pin "1") (pinfunction "A_1") (pintype "passive"))
      (node (ref "C22") (pin "2") (pinfunction "A_2") (pintype "passive"))
      (node (ref "C24") (pin "2") (pinfunction "A_2") (pintype "passive"))
      (node (ref "C25") (pin "1") (pinfunction "A_1") (pintype "passive"))
      (node (ref "C26") (pin "2") (pinfunction "A_2") (pintype "passive"))
      (node (ref "C27") (pin "2") (pinfunction "A_2") (pintype "passive"))
      (node (ref "C28") (pin "1") (pinfunction "A_1") (pintype "passive"))
      (node (ref "C29") (pin "2") (pinfunction "A_2") (pintype "passive"))
      (node (ref "C3") (pin "1") (pinfunction "A_1") (pintype "passive"))
      (node (ref "C30") (pin "1") (pinfunction "A_1") (pintype "passive"))
      (node (ref "C31") (pin "2") (pinfunction "A_2") (pintype "passive"))
      (node (ref "C32") (pin "1") (pinfunction "A_1") (pintype "passive"))
      (node (ref "C33") (pin "2") (pinfunction "A_2") (pintype "passive"))
      (node (ref "C34") (pin "2") (pinfunction "A_2") (pintype "passive"))
      (node (ref "C35") (pin "2") (pinfunction "A_2") (pintype "passive"))
      (node (ref "C36") (pin "2") (pinfunction "A_2") (pintype "passive"))
      (node (ref "C37") (pin "2") (pinfunction "A_2") (pintype "passive"))
      (node (ref "C38") (pin "2") (pinfunction "A_2") (pintype "passive"))
      (node (ref "C39") (pin "2") (pinfunction "A_2") (pintype "passive"))
      (node (ref "C4") (pin "2") (pinfunction "A_2") (pintype "passive"))
      (node (ref "C40") (pin "2") (pinfunction "A_2") (pintype "passive"))
      (node (ref "C41") (pin "2") (pinfunction "A_2") (pintype "passive"))
      (node (ref "C42") (pin "2") (pinfunction "A_2") (pintype "passive"))
      (node (ref "C43") (pin "2") (pinfunction "A_2") (pintype "passive"))
      (node (ref "C44") (pin "1") (pinfunction "A_1") (pintype "passive"))
      (node (ref "C45") (pin "2") (pinfunction "A_2") (pintype "passive"))
      (node (ref "C46") (pin "2") (pinfunction "A_2") (pintype "passive"))
      (node (ref "C47") (pin "1") (pinfunction "A_1") (pintype "passive"))
      (node (ref "C48") (pin "2") (pinfunction "A_2") (pintype "passive"))
      (node (ref "C5") (pin "2") (pinfunction "A_2") (pintype "passive"))
      (node (ref "C6") (pin "2") (pinfunction "A_2") (pintype "passive"))
      (node (ref "C7") (pin "2") (pinfunction "A_2") (pintype "passive"))
      (node (ref "C8") (pin "2") (pinfunction "A_2") (pintype "passive"))
      (node (ref "C9") (pin "1") (pinfunction "A_1") (pintype "passive"))
      (node (ref "DD10") (pin "1") (pinfunction "GND_1") (pintype "passive"))
      (node (ref "DD10") (pin "14") (pinfunction "GND_14") (pintype "passive"))
      (node (ref "DD10") (pin "15") (pinfunction "GND_15") (pintype "passive"))
      (node (ref "DD10") (pin "2") (pinfunction "GND_2") (pintype "passive"))
      (node (ref "DD10") (pin "3") (pinfunction "GND_3") (pintype "passive"))
      (node (ref "DD10") (pin "4") (pinfunction "GND_4") (pintype "passive"))
      (node (ref "DD10") (pin "7") (pinfunction "GND_7") (pintype "passive"))
      (node (ref "DD11") (pin "2") (pinfunction "GND_2") (pintype "passive"))
      (node (ref "DD2") (pin "8") (pinfunction "GND_8") (pintype "passive"))
      (node (ref "DD3") (pin "1") (pinfunction "GND_1") (pintype "passive"))
      (node (ref "DD3") (pin "15") (pinfunction "GND_15") (pintype "passive"))
      (node (ref "DD3") (pin "38") (pinfunction "GND_38") (pintype "passive"))
      (node (ref "DD3") (pin "39") (pinfunction "GND_39") (pintype "passive"))
      (node (ref "DD4") (pin "2") (pinfunction "VM_2") (pintype "passive"))
      (node (ref "DD4") (pin "3") (pinfunction "VM_3") (pintype "passive"))
      (node (ref "DD4") (pin "4") (pinfunction "VM_4") (pintype "passive"))
      (node (ref "DD5") (pin "3") (pinfunction "GND_3") (pintype "passive"))
      (node (ref "DD5") (pin "7") (pinfunction "PGND_7") (pintype "passive"))
      (node (ref "DD5") (pin "9") (pinfunction "PGND_9") (pintype "passive"))
      (node (ref "DD6") (pin "2") (pinfunction "GND_2") (pintype "passive"))
      (node (ref "DD6") (pin "3") (pinfunction "EN_3") (pintype "passive"))
      (node (ref "DD7") (pin "3") (pinfunction "GND_3") (pintype "passive"))
      (node (ref "DD7") (pin "9") (pinfunction "EP_9") (pintype "passive"))
      (node (ref "DD8") (pin "2") (pinfunction "GND_2") (pintype "passive"))
      (node (ref "DD9") (pin "2") (pinfunction "GND_2") (pintype "passive"))
      (node (ref "R10") (pin "1") (pinfunction "A_1") (pintype "passive"))
      (node (ref "R16") (pin "1") (pinfunction "A_1") (pintype "passive"))
      (node (ref "R17") (pin "2") (pinfunction "B_2") (pintype "passive"))
      (node (ref "R20") (pin "1") (pinfunction "A_1") (pintype "passive"))
      (node (ref "R24") (pin "1") (pinfunction "A_1") (pintype "passive"))
      (node (ref "R27") (pin "1") (pinfunction "A_1") (pintype "passive"))
      (node (ref "R28") (pin "1") (pinfunction "A_1") (pintype "passive"))
      (node (ref "R37") (pin "2") (pinfunction "B_2") (pintype "passive"))
      (node (ref "R38") (pin "2") (pinfunction "B_2") (pintype "passive"))
      (node (ref "R41") (pin "1") (pinfunction "A_1") (pintype "passive"))
      (node (ref "R42") (pin "2") (pinfunction "B_2") (pintype "passive"))
      (node (ref "SB1") (pin "2") (pinfunction "2_2") (pintype "passive"))
      (node (ref "SB2") (pin "2") (pinfunction "2_2") (pintype "passive"))
      (node (ref "SB3") (pin "2") (pinfunction "2_2") (pintype "passive"))
      (node (ref "SB4") (pin "2") (pinfunction "2_2") (pintype "passive"))
      (node (ref "SB5") (pin "2") (pinfunction "2_2") (pintype "passive"))
      (node (ref "VD10") (pin "2") (pinfunction "B_2") (pintype "passive"))
      (node (ref "VD11") (pin "2") (pinfunction "B_2") (pintype "passive"))
      (node (ref "VD3") (pin "2") (pinfunction "B_2") (pintype "passive"))
      (node (ref "VD5") (pin "2") (pinfunction "B_2") (pintype "passive"))
      (node (ref "VR1") (pin "3") (pinfunction "C_3") (pintype "passive"))
      (node (ref "VT4") (pin "2") (pinfunction "B_2") (pintype "passive"))
      (node (ref "X2") (pin "2") (pinfunction "2_2") (pintype "passive"))
      (node (ref "XP1") (pin "4") (pinfunction "4_4") (pintype "passive"))
      (node (ref "XP2") (pin "4") (pinfunction "4_4") (pintype "passive"))
      (node (ref "XP3") (pin "1") (pinfunction "1_1") (pintype "passive"))
      (node (ref "XS1") (pin "28") (pinfunction "28_28") (pintype "passive"))
      (node (ref "XS1") (pin "29") (pinfunction "29_29") (pintype "passive"))
      (node (ref "XS1") (pin "3") (pinfunction "3_3") (pintype "passive"))
      (node (ref "XS1") (pin "30") (pinfunction "30_30") (pintype "passive"))
      (node (ref "XS1") (pin "32") (pinfunction "32_32") (pintype "passive"))
      (node (ref "XS1") (pin "34") (pinfunction "34_34") (pintype "passive"))
      (node (ref "XS1") (pin "35") (pinfunction "35_35") (pintype "passive"))
      (node (ref "XS1") (pin "4") (pinfunction "4_4") (pintype "passive"))
      (node (ref "XS1") (pin "45") (pinfunction "45_45") (pintype "passive"))
      (node (ref "XS1") (pin "46") (pinfunction "46_46") (pintype "passive"))
      (node (ref "XS1") (pin "47") (pinfunction "47_47") (pintype "passive"))
      (node (ref "XS1") (pin "48") (pinfunction "48_48") (pintype "passive"))
      (node (ref "XS1") (pin "6") (pinfunction "6_6") (pintype "passive"))
      (node (ref "XS1") (pin "8") (pinfunction "8_8") (pintype "passive"))
      (node (ref "XS1") (pin "9") (pinfunction "9_9") (pintype "passive"))
    )
    (net (code "31") (name "IO12") (class "Default")
      (node (ref "DD3") (pin "14") (pinfunction "IO12_14") (pintype "passive"))
      (node (ref "XP2") (pin "2") (pinfunction "2_2") (pintype "passive"))
    )
    (net (code "32") (name "IO13") (class "Default")
      (node (ref "C13") (pin "2") (pinfunction "A_2") (pintype "passive"))
      (node (ref "C9") (pin "2") (pinfunction "A_2") (pintype "passive"))
      (node (ref "DD3") (pin "16") (pinfunction "IO13_16") (pintype "passive"))
      (node (ref "DD3") (pin "2") (pinfunction "VDD33_2") (pintype "passive"))
      (node (ref "XP2") (pin "3") (pinfunction "3_3") (pintype "passive"))
    )
    (net (code "33") (name "IO14") (class "Default")
      (node (ref "DD3") (pin "13") (pinfunction "IO14_13") (pintype "passive"))
      (node (ref "XP1") (pin "2") (pinfunction "2_2") (pintype "passive"))
    )
    (net (code "34") (name "IO15") (class "Default")
      (node (ref "DD3") (pin "23") (pinfunction "IO15_23") (pintype "passive"))
      (node (ref "XP1") (pin "3") (pinfunction "3_3") (pintype "passive"))
    )
    (net (code "35") (name "IO34") (class "Default")
      (node (ref "C25") (pin "2") (pinfunction "A_2") (pintype "passive"))
      (node (ref "DD3") (pin "6") (pinfunction "IO34_6") (pintype "passive"))
      (node (ref "R13") (pin "1") (pinfunction "A_1") (pintype "passive"))
      (node (ref "SB2") (pin "1") (pinfunction "1_1") (pintype "passive"))
    )
    (net (code "36") (name "IO35") (class "Default")
      (node (ref "C30") (pin "2") (pinfunction "A_2") (pintype "passive"))
      (node (ref "DD3") (pin "7") (pinfunction "IO35_7") (pintype "passive"))
      (node (ref "R21") (pin "1") (pinfunction "A_1") (pintype "passive"))
      (node (ref "SB3") (pin "1") (pinfunction "1_1") (pintype "passive"))
    )
    (net (code "37") (name "ISP_RX") (class "Default")
      (node (ref "R39") (pin "2") (pinfunction "B_2") (pintype "passive"))
      (node (ref "VT6") (pin "2") (pinfunction "B_2") (pintype "passive"))
    )
    (net (code "38") (name "ISP_TX") (class "Default")
      (node (ref "R40") (pin "2") (pinfunction "B_2") (pintype "passive"))
      (node (ref "VT5") (pin "2") (pinfunction "B_2") (pintype "passive"))
    )
    (net (code "39") (name "NEG_CTRL") (class "Default")
      (node (ref "DD2") (pin "7") (pinfunction "QP3_7") (pintype "passive"))
      (node (ref "XP3") (pin "4") (pinfunction "4_4") (pintype "passive"))
    )
    (net (code "40") (name "Net-(DD1-1IN+)") (class "Default")
      (node (ref "DD1") (pin "3") (pinfunction "1IN+_3") (pintype "passive"))
      (node (ref "VR1") (pin "1") (pinfunction "A_1") (pintype "passive"))
    )
    (net (code "41") (name "Net-(DD4-EPAD)") (class "Default")
      (node (ref "C15") (pin "2") (pinfunction "A_2") (pintype "passive"))
      (node (ref "C18") (pin "1") (pinfunction "A_1") (pintype "passive"))
      (node (ref "DD4") (pin "5") (pinfunction "GND_5") (pintype "passive"))
      (node (ref "DD4") (pin "7") (pinfunction "GND_7") (pintype "passive"))
      (node (ref "DD4") (pin "8") (pinfunction "GND_8") (pintype "passive"))
      (node (ref "DD4") (pin "9") (pinfunction "EPAD_9") (pintype "passive"))
      (node (ref "VT1") (pin "1") (pinfunction "A_1") (pintype "passive"))
    )
    (net (code "42") (name "Net-(DD4-VDD)") (class "Default")
      (node (ref "C15") (pin "1") (pinfunction "A_1") (pintype "passive"))
      (node (ref "DD4") (pin "6") (pinfunction "VDD_6") (pintype "passive"))
      (node (ref "R8") (pin "1") (pinfunction "A_1") (pintype "passive"))
    )
    (net (code "43") (name "Net-(DD5-FB2)") (class "Default")
      (node (ref "C16") (pin "1") (pinfunction "A_1") (pintype "passive"))
      (node (ref "DD5") (pin "5") (pinfunction "FB2_5") (pintype "passive"))
      (node (ref "R17") (pin "1") (pinfunction "A_1") (pintype "passive"))
      (node (ref "R18") (pin "2") (pinfunction "B_2") (pintype "passive"))
    )
    (net (code "44") (name "Net-(DD5-NFB1)") (class "Default")
      (node (ref "C23") (pin "2") (pinfunction "A_2") (pintype "passive"))
      (node (ref "DD5") (pin "1") (pinfunction "NFB1_1") (pintype "passive"))
      (node (ref "R15") (pin "1") (pinfunction "A_1") (pintype "passive"))
      (node (ref "R16") (pin "2") (pinfunction "B_2") (pintype "passive"))
    )
    (net (code "45") (name "Net-(DD5-SW1)") (class "Default")
      (node (ref "C20") (pin "2") (pinfunction "A_2") (pintype "passive"))
      (node (ref "DD5") (pin "10") (pinfunction "SW1_10") (pintype "passive"))
      (node (ref "R4") (pin "2") (pinfunction "B_2") (pintype "passive"))
    )
    (net (code "46") (name "Net-(DD5-SW2)") (class "Default")
      (node (ref "DD5") (pin "6") (pinfunction "SW2_6") (pintype "passive"))
      (node (ref "R7") (pin "2") (pinfunction "B_2") (pintype "passive"))
      (node (ref "VD2") (pin "1") (pinfunction "A_1") (pintype "passive"))
    )
    (net (code "47") (name "Net-(DD5-~{SHDN1})") (class "Default")
      (node (ref "DD5") (pin "2") (pinfunction "~{SHDN1}_2") (pintype "passive"))
      (node (ref "R5") (pin "2") (pinfunction "B_2") (pintype "passive"))
    )
    (net (code "48") (name "Net-(DD5-~{SHDN2})") (class "Default")
      (node (ref "DD5") (pin "4") (pinfunction "~{SHDN2}_4") (pintype "passive"))
      (node (ref "R6") (pin "2") (pinfunction "B_2") (pintype "passive"))
    )
    (net (code "49") (name "Net-(DD6-IN)") (class "Default")
      (node (ref "C17") (pin "2") (pinfunction "A_2") (pintype "passive"))
      (node (ref "C19") (pin "2") (pinfunction "A_2") (pintype "passive"))
      (node (ref "DD6") (pin "1") (pinfunction "IN_1") (pintype "passive"))
      (node (ref "R10") (pin "2") (pinfunction "B_2") (pintype "passive"))
      (node (ref "R12") (pin "1") (pinfunction "A_1") (pintype "passive"))
      (node (ref "R9") (pin "2") (pinfunction "B_2") (pintype "passive"))
      (node (ref "VT2") (pin "1") (pinfunction "A_1") (pintype "passive"))
    )
    (net (code "50") (name "Net-(DD7-CHRG)") (class "Default")
      (node (ref "DD7") (pin "6") (pinfunction "CHRG_6") (pintype "passive"))
      (node (ref "VD9") (pin "2") (pinfunction "B_2") (pintype "passive"))
    )
    (net (code "51") (name "Net-(DD7-CT)") (class "Default")
      (node (ref "C31") (pin "1") (pinfunction "A_1") (pintype "passive"))
      (node (ref "DD7") (pin "4") (pinfunction "CT_4") (pintype "passive"))
    )
    (net (code "52") (name "Net-(DD7-Iprog)") (class "Default")
      (node (ref "DD7") (pin "5") (pinfunction "Iprog_5") (pintype "passive"))
      (node (ref "R28") (pin "2") (pinfunction "B_2") (pintype "passive"))
    )
    (net (code "53") (name "Net-(DD7-STDB)") (class "Default")
      (node (ref "DD7") (pin "7") (pinfunction "STDB_7") (pintype "passive"))
      (node (ref "VD8") (pin "2") (pinfunction "B_2") (pintype "passive"))
    )
    (net (code "54") (name "Net-(DD7-Vprog)") (class "Default")
      (node (ref "DD7") (pin "2") (pinfunction "Vprog_2") (pintype "passive"))
      (node (ref "R19") (pin "1") (pinfunction "A_1") (pintype "passive"))
      (node (ref "R20") (pin "2") (pinfunction "B_2") (pintype "passive"))
    )
    (net (code "55") (name "Net-(DD11-D+)") (class "Default")
      (node (ref "DD11") (pin "3") (pinfunction "D+_3") (pintype "passive"))
      (node (ref "R35") (pin "2") (pinfunction "B_2") (pintype "passive"))
    )
    (net (code "56") (name "Net-(DD11-D-)") (class "Default")
      (node (ref "DD11") (pin "4") (pinfunction "D-_4") (pintype "passive"))
      (node (ref "R34") (pin "2") (pinfunction "B_2") (pintype "passive"))
    )
    (net (code "57") (name "Net-(DD11-RST)") (class "Default")
      (node (ref "C45") (pin "1") (pinfunction "A_1") (pintype "passive"))
      (node (ref "DD11") (pin "9") (pinfunction "RST_9") (pintype "passive"))
      (node (ref "R36") (pin "2") (pinfunction "B_2") (pintype "passive"))
    )
    (net (code "58") (name "Net-(DD11-RXD)") (class "Default")
      (node (ref "DD11") (pin "20") (pinfunction "RXD_20") (pintype "passive"))
      (node (ref "R39") (pin "1") (pinfunction "A_1") (pintype "passive"))
    )
    (net (code "59") (name "Net-(DD11-TXD)") (class "Default")
      (node (ref "DD11") (pin "21") (pinfunction "TXD_21") (pintype "passive"))
      (node (ref "R40") (pin "1") (pinfunction "A_1") (pintype "passive"))
    )
    (net (code "60") (name "Net-(DD11-VPP)") (class "Default")
      (node (ref "C47") (pin "2") (pinfunction "A_2") (pintype "passive"))
      (node (ref "DD11") (pin "16") (pinfunction "VPP_16") (pintype "passive"))
    )
    (net (code "61") (name "Net-(R1-A)") (class "Default")
      (node (ref "R1") (pin "1") (pinfunction "A_1") (pintype "passive"))
      (node (ref "VR1") (pin "2") (pinfunction "B_2") (pintype "passive"))
    )
    (net (code "62") (name "Net-(R2-A)") (class "Default")
      (node (ref "R2") (pin "1") (pinfunction "A_1") (pintype "passive"))
      (node (ref "VT1") (pin "2") (pinfunction "B_2") (pintype "passive"))
      (node (ref "X1") (pin "2") (pinfunction "2_2") (pintype "passive"))
    )
    (net (code "63") (name "Net-(R2-B)") (class "Default")
      (node (ref "R2") (pin "2") (pinfunction "B_2") (pintype "passive"))
      (node (ref "VD1") (pin "1") (pinfunction "A_1") (pintype "passive"))
    )
    (net (code "64") (name "Net-(R3-A)") (class "Default")
      (node (ref "R3") (pin "1") (pinfunction "A_1") (pintype "passive"))
      (node (ref "VT1") (pin "3") (pinfunction "C_3") (pintype "passive"))
    )
    (net (code "65") (name "Net-(R12-B)") (class "Default")
      (node (ref "R12") (pin "2") (pinfunction "B_2") (pintype "passive"))
      (node (ref "R14") (pin "1") (pinfunction "A_1") (pintype "passive"))
      (node (ref "VT2") (pin "3") (pinfunction "C_3") (pintype "passive"))
      (node (ref "VT3") (pin "3") (pinfunction "C_3") (pintype "passive"))
    )
    (net (code "66") (name "Net-(R14-B)") (class "Default")
      (node (ref "R14") (pin "2") (pinfunction "B_2") (pintype "passive"))
      (node (ref "VT4") (pin "1") (pinfunction "A_1") (pintype "passive"))
    )
    (net (code "67") (name "Net-(R22-A)") (class "Default")
      (node (ref "R22") (pin "1") (pinfunction "A_1") (pintype "passive"))
      (node (ref "VT4") (pin "3") (pinfunction "C_3") (pintype "passive"))
    )
    (net (code "68") (name "Net-(R22-B)") (class "Default")
      (node (ref "R22") (pin "2") (pinfunction "B_2") (pintype "passive"))
      (node (ref "R24") (pin "2") (pinfunction "B_2") (pintype "passive"))
      (node (ref "VD6") (pin "2") (pinfunction "2_2") (pintype "passive"))
      (node (ref "VD7") (pin "2") (pinfunction "2_2") (pintype "passive"))
    )
    (net (code "69") (name "Net-(R23-B)") (class "Default")
      (node (ref "R23") (pin "2") (pinfunction "B_2") (pintype "passive"))
      (node (ref "VD5") (pin "1") (pinfunction "A_1") (pintype "passive"))
    )
    (net (code "70") (name "Net-(R29-A)") (class "Default")
      (node (ref "R29") (pin "1") (pinfunction "A_1") (pintype "passive"))
      (node (ref "VD8") (pin "1") (pinfunction "A_1") (pintype "passive"))
    )
    (net (code "71") (name "Net-(R30-A)") (class "Default")
      (node (ref "R30") (pin "1") (pinfunction "A_1") (pintype "passive"))
      (node (ref "VD9") (pin "1") (pinfunction "A_1") (pintype "passive"))
    )
    (net (code "72") (name "Net-(R31-A)") (class "Default")
      (node (ref "C36") (pin "1") (pinfunction "A_1") (pintype "passive"))
      (node (ref "R31") (pin "1") (pinfunction "A_1") (pintype "passive"))
    )
    (net (code "73") (name "Net-(R32-A)") (class "Default")
      (node (ref "R32") (pin "1") (pinfunction "A_1") (pintype "passive"))
      (node (ref "VT5") (pin "3") (pinfunction "C_3") (pintype "passive"))
    )
    (net (code "74") (name "Net-(R33-A)") (class "Default")
      (node (ref "R33") (pin "1") (pinfunction "A_1") (pintype "passive"))
      (node (ref "VT6") (pin "3") (pinfunction "C_3") (pintype "passive"))
    )
    (net (code "75") (name "Net-(VD3-A)") (class "Default")
      (node (ref "C20") (pin "1") (pinfunction "A_1") (pintype "passive"))
      (node (ref "VD3") (pin "1") (pinfunction "A_1") (pintype "passive"))
      (node (ref "VD4") (pin "2") (pinfunction "B_2") (pintype "passive"))
    )
    (net (code "76") (name "POS_CTRL") (class "Default")
      (node (ref "DD2") (pin "6") (pinfunction "QP2_6") (pintype "passive"))
      (node (ref "XP3") (pin "3") (pinfunction "3_3") (pintype "passive"))
    )
    (net (code "77") (name "PWR_EN") (class "Default")
      (node (ref "DD2") (pin "13") (pinfunction "QP5_13") (pintype "passive"))
      (node (ref "VD7") (pin "1") (pinfunction "1_1") (pintype "passive"))
    )
    (net (code "78") (name "RTS") (class "Default")
      (node (ref "DD11") (pin "19") (pinfunction "RTS_19") (pintype "passive"))
      (node (ref "DD12") (pin "1") (pinfunction "E1_1") (pintype "passive"))
      (node (ref "DD12") (pin "5") (pinfunction "B2_5") (pintype "passive"))
    )
    (net (code "79") (name "SENSOR_VN") (class "Default")
      (node (ref "C21") (pin "2") (pinfunction "A_2") (pintype "passive"))
      (node (ref "DD3") (pin "5") (pinfunction "S_VN_5") (pintype "passive"))
      (node (ref "R11") (pin "1") (pinfunction "A_1") (pintype "passive"))
      (node (ref "SB1") (pin "1") (pinfunction "1_1") (pintype "passive"))
    )
    (net (code "80") (name "SMPS_CTRL") (class "Default")
      (node (ref "DD2") (pin "5") (pinfunction "QP1_5") (pintype "passive"))
      (node (ref "XP3") (pin "2") (pinfunction "2_2") (pintype "passive"))
    )
    (net (code "81") (name "STR_IO0") (class "Default")
      (node (ref "DD12") (pin "3") (pinfunction "C2_3") (pintype "passive"))
      (node (ref "DD2") (pin "1") (pinfunction "STR_1") (pintype "passive"))
      (node (ref "DD3") (pin "25") (pinfunction "IO0_25") (pintype "passive"))
      (node (ref "SB5") (pin "1") (pinfunction "1_1") (pintype "passive"))
    )
    (net (code "82") (name "UAR0_RX") (class "Default")
      (node (ref "DD3") (pin "34") (pinfunction "RXD0_34") (pintype "passive"))
      (node (ref "VT5") (pin "1") (pinfunction "A_1") (pintype "passive"))
    )
    (net (code "83") (name "UAR0_TX") (class "Default")
      (node (ref "DD3") (pin "35") (pinfunction "TXD0_35") (pintype "passive"))
      (node (ref "VT6") (pin "1") (pinfunction "A_1") (pintype "passive"))
    )
    (net (code "84") (name "USB1_N") (class "Default")
      (node (ref "C42") (pin "1") (pinfunction "A_1") (pintype "passive"))
      (node (ref "DD10") (pin "11") (pinfunction "DN1-_11") (pintype "passive"))
      (node (ref "DD10") (pin "19") (pinfunction "DN-_19") (pintype "passive"))
      (node (ref "R35") (pin "1") (pinfunction "A_1") (pintype "passive"))
      (node (ref "VD10") (pin "1") (pinfunction "A_1") (pintype "passive"))
    )
    (net (code "85") (name "USB1_P") (class "Default")
      (node (ref "C41") (pin "1") (pinfunction "A_1") (pintype "passive"))
      (node (ref "DD10") (pin "10") (pinfunction "DP1+_10") (pintype "passive"))
      (node (ref "DD10") (pin "18") (pinfunction "DP+_18") (pintype "passive"))
      (node (ref "R34") (pin "1") (pinfunction "A_1") (pintype "passive"))
      (node (ref "VD11") (pin "1") (pinfunction "A_1") (pintype "passive"))
    )
    (net (code "86") (name "VBAT") (class "Default")
      (node (ref "C22") (pin "1") (pinfunction "A_1") (pintype "passive"))
      (node (ref "C24") (pin "1") (pinfunction "A_1") (pintype "passive"))
      (node (ref "C46") (pin "1") (pinfunction "A_1") (pintype "passive"))
      (node (ref "C48") (pin "1") (pinfunction "A_1") (pintype "passive"))
      (node (ref "DD7") (pin "1") (pinfunction "BAT_1") (pintype "passive"))
      (node (ref "R19") (pin "2") (pinfunction "B_2") (pintype "passive"))
      (node (ref "R3") (pin "2") (pinfunction "B_2") (pintype "passive"))
      (node (ref "R41") (pin "2") (pinfunction "B_2") (pintype "passive"))
      (node (ref "R8") (pin "2") (pinfunction "B_2") (pintype "passive"))
      (node (ref "VD1") (pin "2") (pinfunction "B_2") (pintype "passive"))
      (node (ref "VT7") (pin "1") (pinfunction "A_1") (pintype "passive"))
      (node (ref "X1") (pin "1") (pinfunction "1_1") (pintype "passive"))
      (node (ref "X2") (pin "1") (pinfunction "1_1") (pintype "passive"))
    )
    (net (code "87") (name "VBUS") (class "Default")
      (node (ref "C39") (pin "1") (pinfunction "A_1") (pintype "passive"))
      (node (ref "C40") (pin "1") (pinfunction "A_1") (pintype "passive"))
      (node (ref "C44") (pin "2") (pinfunction "A_2") (pintype "passive"))
      (node (ref "DD10") (pin "13") (pinfunction "UBUS2_13") (pintype "passive"))
      (node (ref "DD10") (pin "16") (pinfunction "PWR_16") (pintype "passive"))
      (node (ref "DD10") (pin "8") (pinfunction "UBUS1_8") (pintype "passive"))
      (node (ref "DD11") (pin "7") (pinfunction "REGIN_7") (pintype "passive"))
      (node (ref "DD11") (pin "8") (pinfunction "VBUS_8") (pintype "passive"))
      (node (ref "DD7") (pin "8") (pinfunction "VDD_8") (pintype "passive"))
      (node (ref "R29") (pin "2") (pinfunction "B_2") (pintype "passive"))
      (node (ref "R30") (pin "2") (pinfunction "B_2") (pintype "passive"))
      (node (ref "R31") (pin "2") (pinfunction "B_2") (pintype "passive"))
      (node (ref "R42") (pin "1") (pinfunction "A_1") (pintype "passive"))
      (node (ref "VD12") (pin "1") (pinfunction "A_1") (pintype "passive"))
      (node (ref "VD6") (pin "1") (pinfunction "1_1") (pintype "passive"))
      (node (ref "VT7") (pin "3") (pinfunction "C_3") (pintype "passive"))
    )
    (net (code "88") (name "VDD3V3") (class "Default")
      (node (ref "C11") (pin "2") (pinfunction "A_2") (pintype "passive"))
      (node (ref "C12") (pin "2") (pinfunction "A_2") (pintype "passive"))
      (node (ref "DD2") (pin "15") (pinfunction "OE_15") (pintype "passive"))
      (node (ref "DD2") (pin "16") (pinfunction "VCC_16") (pintype "passive"))
      (node (ref "R11") (pin "2") (pinfunction "B_2") (pintype "passive"))
      (node (ref "R13") (pin "2") (pinfunction "B_2") (pintype "passive"))
      (node (ref "R21") (pin "2") (pinfunction "B_2") (pintype "passive"))
      (node (ref "R25") (pin "2") (pinfunction "B_2") (pintype "passive"))
    )
    (net (code "89") (name "VDDV3") (class "Default")
      (node (ref "C26") (pin "1") (pinfunction "A_1") (pintype "passive"))
      (node (ref "C29") (pin "1") (pinfunction "A_1") (pintype "passive"))
      (node (ref "DD6") (pin "5") (pinfunction "OUT_5") (pintype "passive"))
      (node (ref "VT3") (pin "1") (pinfunction "A_1") (pintype "passive"))
    )
    (net (code "90") (name "VDD_UART") (class "Default")
      (node (ref "C38") (pin "1") (pinfunction "A_1") (pintype "passive"))
      (node (ref "DD11") (pin "5") (pinfunction "VIO_5") (pintype "passive"))
      (node (ref "DD11") (pin "6") (pinfunction "VDD_6") (pintype "passive"))
      (node (ref "R32") (pin "2") (pinfunction "B_2") (pintype "passive"))
      (node (ref "R33") (pin "2") (pinfunction "B_2") (pintype "passive"))
      (node (ref "R36") (pin "1") (pinfunction "A_1") (pintype "passive"))
      (node (ref "R37") (pin "1") (pinfunction "A_1") (pintype "passive"))
    )
    (net (code "91") (name "unconnected-(DD1-2IN+-Pad5)") (class "Default")
      (node (ref "DD1") (pin "5") (pinfunction "2IN+_5") (pintype "passive"))
    )
    (net (code "92") (name "unconnected-(DD1-2IN--Pad6)") (class "Default")
      (node (ref "DD1") (pin "6") (pinfunction "2IN-_6") (pintype "passive"))
    )
    (net (code "93") (name "unconnected-(DD1-2OUT-Pad7)") (class "Default")
      (node (ref "DD1") (pin "7") (pinfunction "2OUT_7") (pintype "passive"))
    )
    (net (code "94") (name "unconnected-(DD2-QS1-Pad9)") (class "Default")
      (node (ref "DD2") (pin "9") (pinfunction "QS1_9") (pintype "passive"))
    )
    (net (code "95") (name "unconnected-(DD2-QS2-Pad10)") (class "Default")
      (node (ref "DD2") (pin "10") (pinfunction "QS2_10") (pintype "passive"))
    )
    (net (code "96") (name "unconnected-(DD3-CLK-Pad20)") (class "Default")
      (node (ref "DD3") (pin "20") (pinfunction "CLK_20") (pintype "passive"))
    )
    (net (code "97") (name "unconnected-(DD3-CMD-Pad19)") (class "Default")
      (node (ref "DD3") (pin "19") (pinfunction "CMD_19") (pintype "passive"))
    )
    (net (code "98") (name "unconnected-(DD3-NC-Pad27)") (class "Default")
      (node (ref "DD3") (pin "27") (pinfunction "NC_27") (pintype "passive"))
    )
    (net (code "99") (name "unconnected-(DD3-NC-Pad28)") (class "Default")
      (node (ref "DD3") (pin "28") (pinfunction "NC_28") (pintype "passive"))
    )
    (net (code "100") (name "unconnected-(DD3-NC-Pad32)") (class "Default")
      (node (ref "DD3") (pin "32") (pinfunction "NC_32") (pintype "passive"))
    )
    (net (code "101") (name "unconnected-(DD3-SD0-Pad21)") (class "Default")
      (node (ref "DD3") (pin "21") (pinfunction "SD0_21") (pintype "passive"))
    )
    (net (code "102") (name "unconnected-(DD3-SD1-Pad22)") (class "Default")
      (node (ref "DD3") (pin "22") (pinfunction "SD1_22") (pintype "passive"))
    )
    (net (code "103") (name "unconnected-(DD3-SD2-Pad17)") (class "Default")
      (node (ref "DD3") (pin "17") (pinfunction "SD2_17") (pintype "passive"))
    )
    (net (code "104") (name "unconnected-(DD3-SD3-Pad18)") (class "Default")
      (node (ref "DD3") (pin "18") (pinfunction "SD3_18") (pintype "passive"))
    )
    (net (code "105") (name "unconnected-(DD4-NC-Pad1)") (class "Default")
      (node (ref "DD4") (pin "1") (pinfunction "NC_1") (pintype "passive"))
    )
    (net (code "106") (name "unconnected-(DD6-NC-Pad4)") (class "Default")
      (node (ref "DD6") (pin "4") (pinfunction "NC_4") (pintype "passive"))
    )
    (net (code "107") (name "unconnected-(DD10-GND-Pad22)") (class "Default")
      (node (ref "DD10") (pin "22") (pinfunction "GND_22") (pintype "passive"))
    )
    (net (code "108") (name "unconnected-(DD10-NC-Pad5)") (class "Default")
      (node (ref "DD10") (pin "5") (pinfunction "NC_5") (pintype "passive"))
    )
    (net (code "109") (name "unconnected-(DD10-NC-Pad6)") (class "Default")
      (node (ref "DD10") (pin "6") (pinfunction "NC_6") (pintype "passive"))
    )
    (net (code "110") (name "unconnected-(DD10-PWR1-Pad21)") (class "Default")
      (node (ref "DD10") (pin "21") (pinfunction "PWR1_21") (pintype "passive"))
    )
    (net (code "111") (name "unconnected-(DD10-SUB1-Pad12)") (class "Default")
      (node (ref "DD10") (pin "12") (pinfunction "SUB1_12") (pintype "passive"))
    )
    (net (code "112") (name "unconnected-(DD10-VCONN-Pad17)") (class "Default")
      (node (ref "DD10") (pin "17") (pinfunction "VCONN_17") (pintype "passive"))
    )
    (net (code "113") (name "unconnected-(DD11-CTS-Pad18)") (class "Default")
      (node (ref "DD11") (pin "18") (pinfunction "CTS_18") (pintype "passive"))
    )
    (net (code "114") (name "unconnected-(DD11-DCD-Pad24)") (class "Default")
      (node (ref "DD11") (pin "24") (pinfunction "DCD_24") (pintype "passive"))
    )
    (net (code "115") (name "unconnected-(DD11-DSR-Pad22)") (class "Default")
      (node (ref "DD11") (pin "22") (pinfunction "DSR_22") (pintype "passive"))
    )
    (net (code "116") (name "unconnected-(DD11-GPIO0-Pad14)") (class "Default")
      (node (ref "DD11") (pin "14") (pinfunction "GPIO0_14") (pintype "passive"))
    )
    (net (code "117") (name "unconnected-(DD11-GPIO1-Pad13)") (class "Default")
      (node (ref "DD11") (pin "13") (pinfunction "GPIO1_13") (pintype "passive"))
    )
    (net (code "118") (name "unconnected-(DD11-GPIO2-Pad12)") (class "Default")
      (node (ref "DD11") (pin "12") (pinfunction "GPIO2_12") (pintype "passive"))
    )
    (net (code "119") (name "unconnected-(DD11-GPIO3-Pad11)") (class "Default")
      (node (ref "DD11") (pin "11") (pinfunction "GPIO3_11") (pintype "passive"))
    )
    (net (code "120") (name "unconnected-(DD11-NC-Pad10)") (class "Default")
      (node (ref "DD11") (pin "10") (pinfunction "NC_10") (pintype "passive"))
    )
    (net (code "121") (name "unconnected-(DD11-R1-Pad1)") (class "Default")
      (node (ref "DD11") (pin "1") (pinfunction "R1_1") (pintype "passive"))
    )
    (net (code "122") (name "unconnected-(DD11-S_HIGH-Pad17)") (class "Default")
      (node (ref "DD11") (pin "17") (pinfunction "S_HIGH_17") (pintype "passive"))
    )
    (net (code "123") (name "unconnected-(DD11-S_LOW-Pad15)") (class "Default")
      (node (ref "DD11") (pin "15") (pinfunction "S_LOW_15") (pintype "passive"))
    )
    (net (code "124") (name "unconnected-(XS1-Pad5)") (class "Default")
      (node (ref "XS1") (pin "5") (pinfunction "5_5") (pintype "passive"))
    )
    (net (code "125") (name "unconnected-(XS1-Pad22)") (class "Default")
      (node (ref "XS1") (pin "22") (pinfunction "22_22") (pintype "passive"))
    )
    (net (code "126") (name "unconnected-(XS1-Pad39)") (class "Default")
      (node (ref "XS1") (pin "39") (pinfunction "39_39") (pintype "passive"))
    )
    (net (code "127") (name "unconnected-(XS1-Pad40)") (class "Default")
      (node (ref "XS1") (pin "40") (pinfunction "40_40") (pintype "passive"))
    )
    (net (code "128") (name "unconnected-(XS1-Pad41)") (class "Default")
      (node (ref "XS1") (pin "41") (pinfunction "41_41") (pintype "passive"))
    )
    (net (code "129") (name "unconnected-(XS1-Pad42)") (class "Default")
      (node (ref "XS1") (pin "42") (pinfunction "42_42") (pintype "passive"))
    )
    (net (code "130") (name "unconnected-(XS1-Pad43)") (class "Default")
      (node (ref "XS1") (pin "43") (pinfunction "43_43") (pintype "passive"))
    )
    (net (code "131") (name "unconnected-(XS1-Pad44)") (class "Default")
      (node (ref "XS1") (pin "44") (pinfunction "44_44") (pintype "passive"))
    )
  )
)
